# POWER.net
KiCad netlist of a schematic drawn in Altium Designer
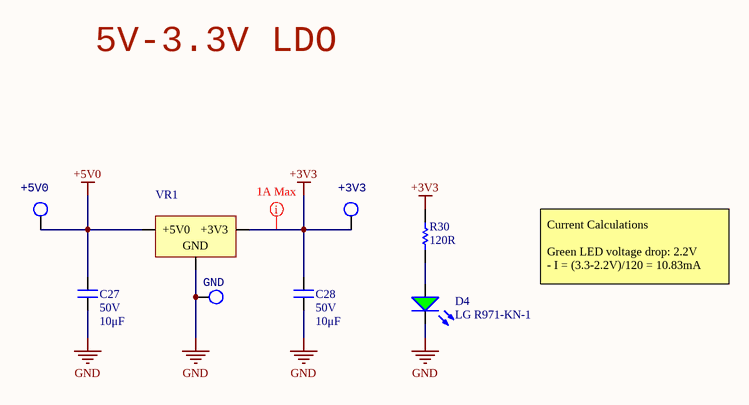
[diagram p0: POWER.SchDoc]

(export (version "E")
  (design (tool "Eeschema 10.0.6"))
  (components
    (comp (ref "+3V3")
      (value "TESTPOINT_LOOP")
      (footprint "TESTPOINT_LOOP")
      (description "Loop testpoint through-hole pad")
      (libsource (lib "UWRT_Schematic_Library_2020") (part "TESTPOINT_LOOP"))
    )
    (comp (ref "+5V0")
      (value "TESTPOINT_LOOP")
      (footprint "TESTPOINT_LOOP")
      (description "Loop testpoint through-hole pad")
      (libsource (lib "UWRT_Schematic_Library_2020") (part "TESTPOINT_LOOP"))
    )
    (comp (ref "C27")
      (value "10μF")
      (footprint "CAPC1206(3216)")
      (description "CAP CER 10UF 50V X5R 1206")
      (fields (field (name "VOLTAGE RATING") "50V") (field (name "Comment") "10uF"))
      (libsource (lib "UWRT_Schematic_Library_2020") (part "CAP_10uF_50V_1206"))
    )
    (comp (ref "C28")
      (value "10μF")
      (footprint "CAPC1206(3216)")
      (description "CAP CER 10UF 50V X5R 1206")
      (fields (field (name "VOLTAGE RATING") "50V") (field (name "Comment") "10uF"))
      (libsource (lib "UWRT_Schematic_Library_2020") (part "CAP_10uF_50V_1206"))
    )
    (comp (ref "D4")
      (value "LG R971-KN-1")
      (footprint "LED_0805_LINE")
      (description "LED GREEN DIFFUSED 0805 SMD")
      (libsource (lib "UWRT_Schematic_Library_2020") (part "DIO_LED_G"))
    )
    (comp (ref "GND")
      (value "TESTPOINT_LOOP")
      (footprint "TESTPOINT_LOOP")
      (description "Loop testpoint through-hole pad")
      (libsource (lib "UWRT_Schematic_Library_2020") (part "TESTPOINT_LOOP"))
    )
    (comp (ref "R30")
      (value "120R")
      (footprint "RESC0603(1608)_N")
      (description "RES SMD 120 OHM 5% 1/10W 0603")
      (fields (field (name "MANUFACTURER") "Yageo") (field (name "MPN") "RC0603JR-07120RL"))
      (libsource (lib "UWRT_Schematic_Library_2020") (part "RES_120R_0603"))
    )
    (comp (ref "VR1")
      (value "5V0_3V3_LDO")
      (footprint "D2PAK_M")
      (description "IC REG LINEAR 3.3V 1A DPAK")
      (libsource (lib "UWRT_Schematic_Library_2020") (part "5V0_3V3_LDO"))
    )
  )
  (nets
    (net (code "1") (name "+3V3") (class "Default")
      (node (ref "+3V3") (pin "1") (pintype "passive"))
      (node (ref "C28") (pin "1") (pinfunction "1_1") (pintype "passive"))
      (node (ref "R30") (pin "2") (pinfunction "2_2") (pintype "passive"))
      (node (ref "VR1") (pin "2") (pinfunction "+3V3_2") (pintype "passive"))
    )
    (net (code "2") (name "+5V0") (class "Default")
      (node (ref "+5V0") (pin "1") (pintype "passive"))
      (node (ref "C27") (pin "1") (pinfunction "1_1") (pintype "passive"))
      (node (ref "VR1") (pin "3") (pinfunction "+5V0_3") (pintype "passive"))
    )
    (net (code "3") (name "GND") (class "Default")
      (node (ref "C27") (pin "2") (pinfunction "2_2") (pintype "passive"))
      (node (ref "C28") (pin "2") (pinfunction "2_2") (pintype "passive"))
      (node (ref "D4") (pin "2") (pinfunction "K_2") (pintype "passive"))
      (node (ref "GND") (pin "1") (pintype "passive"))
      (node (ref "VR1") (pin "1") (pinfunction "GND_1") (pintype "passive"))
    )
    (net (code "4") (name "Net-(D4-A)") (class "Default")
      (node (ref "D4") (pin "1") (pinfunction "A_1") (pintype "passive"))
      (node (ref "R30") (pin "1") (pinfunction "1_1") (pintype "passive"))
    )
  )
)
